# LED-Holder_5mm.net
KiCad netlist of a schematic drawn in Altium Designer
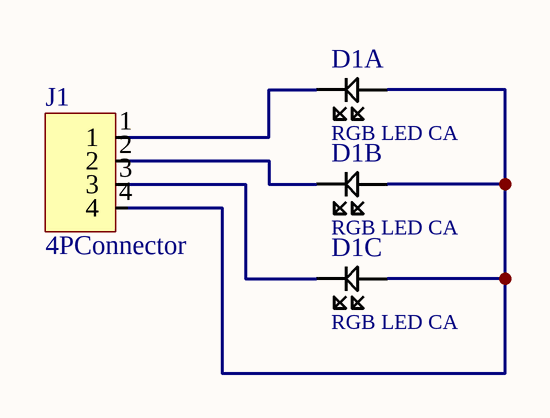
[diagram p0: LED-Holder_5mm.SchDoc]

(export (version "E")
  (design (tool "Eeschema 10.0.6"))
  (components
    (comp (ref "D1")
      (value "RGB LED CA")
      (footprint "RGB-LED_Through Hole")
      (description "5mm")
      (libsource (lib "OVLib") (part "LED_RGB_CA"))
    )
    (comp (ref "J1")
      (value "4PConnector")
      (footprint "JST_B4B-PH-K-S")
      (description "JST PH-Series 2mm Pitch")
      (libsource (lib "OVLib") (part "4PConnector"))
    )
  )
  (nets
    (net (code "1") (name "Net-(D1-Pad1)") (class "Default")
      (node (ref "D1") (pin "1") (pinfunction "1_1") (pintype "passive"))
      (node (ref "J1") (pin "1") (pinfunction "1_1") (pintype "passive"))
    )
    (net (code "2") (name "Net-(D1-Pad2)") (class "Default")
      (node (ref "D1") (pin "2") (pinfunction "2_2") (pintype "passive"))
      (node (ref "J1") (pin "4") (pinfunction "4_4") (pintype "passive"))
    )
    (net (code "3") (name "Net-(D1-Pad3)") (class "Default")
      (node (ref "D1") (pin "3") (pinfunction "3_3") (pintype "passive"))
      (node (ref "J1") (pin "2") (pinfunction "2_2") (pintype "passive"))
    )
    (net (code "4") (name "Net-(D1-Pad4)") (class "Default")
      (node (ref "D1") (pin "4") (pinfunction "4_4") (pintype "passive"))
      (node (ref "J1") (pin "3") (pinfunction "3_3") (pintype "passive"))
    )
  )
)
